# LED.net
KiCad netlist of a schematic drawn in Altium Designer
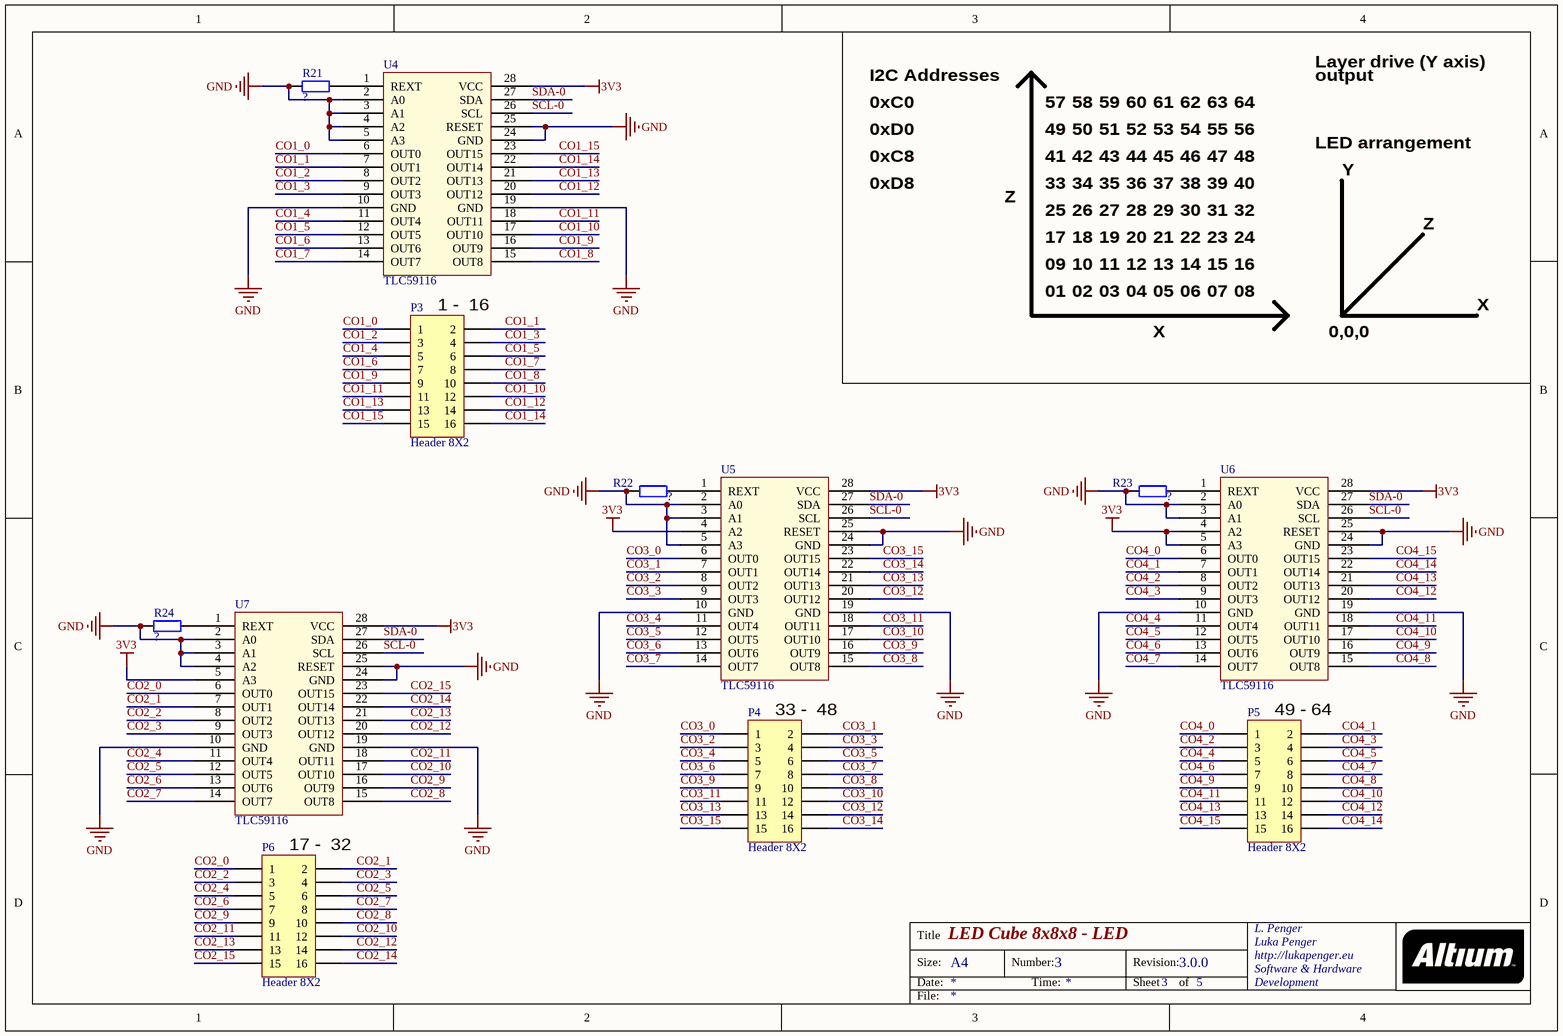
[diagram p0: LED.SchDoc]

(export (version "E")
  (design (tool "Eeschema 10.0.6"))
  (components
    (comp (ref "P3")
      (value "Header 8X2")
      (footprint "IDC-2x8")
      (description "Header, 8-Pin, Dual row")
      (fields (field (name "PUBLISHER") "Altium Limited"))
      (libsource (lib "Miscellaneous Connectors") (part "Header 8X2"))
    )
    (comp (ref "P4")
      (value "Header 8X2")
      (footprint "IDC-2x8")
      (description "Header, 8-Pin, Dual row")
      (fields (field (name "PUBLISHER") "Altium Limited"))
      (libsource (lib "Miscellaneous Connectors") (part "Header 8X2"))
    )
    (comp (ref "P5")
      (value "Header 8X2")
      (footprint "IDC-2x8")
      (description "Header, 8-Pin, Dual row")
      (fields (field (name "PUBLISHER") "Altium Limited"))
      (libsource (lib "Miscellaneous Connectors") (part "Header 8X2"))
    )
    (comp (ref "P6")
      (value "Header 8X2")
      (footprint "IDC-2x8")
      (description "Header, 8-Pin, Dual row")
      (fields (field (name "PUBLISHER") "Altium Limited"))
      (libsource (lib "Miscellaneous Connectors") (part "Header 8X2"))
    )
    (comp (ref "R21")
      (value "?")
      (footprint "1608[0603]")
      (description "Resistor")
      (fields (field (name "PUBLISHER") "Altium Limited"))
      (libsource (lib "Miscellaneous Devices") (part "Res2"))
    )
    (comp (ref "R22")
      (value "?")
      (footprint "1608[0603]")
      (description "Resistor")
      (fields (field (name "PUBLISHER") "Altium Limited"))
      (libsource (lib "") (part "Res2_1"))
    )
    (comp (ref "R23")
      (value "?")
      (footprint "1608[0603]")
      (description "Resistor")
      (fields (field (name "PUBLISHER") "Altium Limited"))
      (libsource (lib "") (part "Res2_1"))
    )
    (comp (ref "R24")
      (value "?")
      (footprint "1608[0603]")
      (description "Resistor")
      (fields (field (name "PUBLISHER") "Altium Limited"))
      (libsource (lib "Miscellaneous Devices") (part "Res2"))
    )
    (comp (ref "U4")
      (value "TLC59116")
      (footprint "TSSOP28")
      (description "16-Channel i2c LED driver")
      (libsource (lib "LukaLIBRARY") (part "TLC59116"))
    )
    (comp (ref "U5")
      (value "TLC59116")
      (footprint "TSSOP28")
      (description "16-Channel i2c LED driver")
      (libsource (lib "LukaLIBRARY") (part "TLC59116"))
    )
    (comp (ref "U6")
      (value "TLC59116")
      (footprint "TSSOP28")
      (description "16-Channel i2c LED driver")
      (libsource (lib "LukaLIBRARY") (part "TLC59116"))
    )
    (comp (ref "U7")
      (value "TLC59116")
      (footprint "TSSOP28")
      (description "16-Channel i2c LED driver")
      (libsource (lib "LukaLIBRARY") (part "TLC59116"))
    )
  )
  (nets
    (net (code "1") (name "/CO1_0") (class "Default")
      (node (ref "P3") (pin "1") (pinfunction "1_1") (pintype "passive"))
      (node (ref "U4") (pin "6") (pinfunction "OUT0_6") (pintype "passive"))
    )
    (net (code "2") (name "/CO1_1") (class "Default")
      (node (ref "P3") (pin "2") (pinfunction "2_2") (pintype "passive"))
      (node (ref "U4") (pin "7") (pinfunction "OUT1_7") (pintype "passive"))
    )
    (net (code "3") (name "/CO1_2") (class "Default")
      (node (ref "P3") (pin "3") (pinfunction "3_3") (pintype "passive"))
      (node (ref "U4") (pin "8") (pinfunction "OUT2_8") (pintype "passive"))
    )
    (net (code "4") (name "/CO1_3") (class "Default")
      (node (ref "P3") (pin "4") (pinfunction "4_4") (pintype "passive"))
      (node (ref "U4") (pin "9") (pinfunction "OUT3_9") (pintype "passive"))
    )
    (net (code "5") (name "/CO1_4") (class "Default")
      (node (ref "P3") (pin "5") (pinfunction "5_5") (pintype "passive"))
      (node (ref "U4") (pin "11") (pinfunction "OUT4_11") (pintype "passive"))
    )
    (net (code "6") (name "/CO1_5") (class "Default")
      (node (ref "P3") (pin "6") (pinfunction "6_6") (pintype "passive"))
      (node (ref "U4") (pin "12") (pinfunction "OUT5_12") (pintype "passive"))
    )
    (net (code "7") (name "/CO1_6") (class "Default")
      (node (ref "P3") (pin "7") (pinfunction "7_7") (pintype "passive"))
      (node (ref "U4") (pin "13") (pinfunction "OUT6_13") (pintype "passive"))
    )
    (net (code "8") (name "/CO1_7") (class "Default")
      (node (ref "P3") (pin "8") (pinfunction "8_8") (pintype "passive"))
      (node (ref "U4") (pin "14") (pinfunction "OUT7_14") (pintype "passive"))
    )
    (net (code "9") (name "/CO1_8") (class "Default")
      (node (ref "P3") (pin "10") (pinfunction "10_10") (pintype "passive"))
      (node (ref "U4") (pin "15") (pinfunction "OUT8_15") (pintype "passive"))
    )
    (net (code "10") (name "/CO1_9") (class "Default")
      (node (ref "P3") (pin "9") (pinfunction "9_9") (pintype "passive"))
      (node (ref "U4") (pin "16") (pinfunction "OUT9_16") (pintype "passive"))
    )
    (net (code "11") (name "/CO1_10") (class "Default")
      (node (ref "P3") (pin "12") (pinfunction "12_12") (pintype "passive"))
      (node (ref "U4") (pin "17") (pinfunction "OUT10_17") (pintype "passive"))
    )
    (net (code "12") (name "/CO1_11") (class "Default")
      (node (ref "P3") (pin "11") (pinfunction "11_11") (pintype "passive"))
      (node (ref "U4") (pin "18") (pinfunction "OUT11_18") (pintype "passive"))
    )
    (net (code "13") (name "/CO1_12") (class "Default")
      (node (ref "P3") (pin "14") (pinfunction "14_14") (pintype "passive"))
      (node (ref "U4") (pin "20") (pinfunction "OUT12_20") (pintype "passive"))
    )
    (net (code "14") (name "/CO1_13") (class "Default")
      (node (ref "P3") (pin "13") (pinfunction "13_13") (pintype "passive"))
      (node (ref "U4") (pin "21") (pinfunction "OUT13_21") (pintype "passive"))
    )
    (net (code "15") (name "/CO1_14") (class "Default")
      (node (ref "P3") (pin "16") (pinfunction "16_16") (pintype "passive"))
      (node (ref "U4") (pin "22") (pinfunction "OUT14_22") (pintype "passive"))
    )
    (net (code "16") (name "/CO1_15") (class "Default")
      (node (ref "P3") (pin "15") (pinfunction "15_15") (pintype "passive"))
      (node (ref "U4") (pin "23") (pinfunction "OUT15_23") (pintype "passive"))
    )
    (net (code "17") (name "/CO2_0") (class "Default")
      (node (ref "P6") (pin "1") (pinfunction "1_1") (pintype "passive"))
      (node (ref "U7") (pin "6") (pinfunction "OUT0_6") (pintype "passive"))
    )
    (net (code "18") (name "/CO2_1") (class "Default")
      (node (ref "P6") (pin "2") (pinfunction "2_2") (pintype "passive"))
      (node (ref "U7") (pin "7") (pinfunction "OUT1_7") (pintype "passive"))
    )
    (net (code "19") (name "/CO2_2") (class "Default")
      (node (ref "P6") (pin "3") (pinfunction "3_3") (pintype "passive"))
      (node (ref "U7") (pin "8") (pinfunction "OUT2_8") (pintype "passive"))
    )
    (net (code "20") (name "/CO2_3") (class "Default")
      (node (ref "P6") (pin "4") (pinfunction "4_4") (pintype "passive"))
      (node (ref "U7") (pin "9") (pinfunction "OUT3_9") (pintype "passive"))
    )
    (net (code "21") (name "/CO2_4") (class "Default")
      (node (ref "P6") (pin "5") (pinfunction "5_5") (pintype "passive"))
      (node (ref "U7") (pin "11") (pinfunction "OUT4_11") (pintype "passive"))
    )
    (net (code "22") (name "/CO2_5") (class "Default")
      (node (ref "P6") (pin "6") (pinfunction "6_6") (pintype "passive"))
      (node (ref "U7") (pin "12") (pinfunction "OUT5_12") (pintype "passive"))
    )
    (net (code "23") (name "/CO2_6") (class "Default")
      (node (ref "P6") (pin "7") (pinfunction "7_7") (pintype "passive"))
      (node (ref "U7") (pin "13") (pinfunction "OUT6_13") (pintype "passive"))
    )
    (net (code "24") (name "/CO2_7") (class "Default")
      (node (ref "P6") (pin "8") (pinfunction "8_8") (pintype "passive"))
      (node (ref "U7") (pin "14") (pinfunction "OUT7_14") (pintype "passive"))
    )
    (net (code "25") (name "/CO2_8") (class "Default")
      (node (ref "P6") (pin "10") (pinfunction "10_10") (pintype "passive"))
      (node (ref "U7") (pin "15") (pinfunction "OUT8_15") (pintype "passive"))
    )
    (net (code "26") (name "/CO2_9") (class "Default")
      (node (ref "P6") (pin "9") (pinfunction "9_9") (pintype "passive"))
      (node (ref "U7") (pin "16") (pinfunction "OUT9_16") (pintype "passive"))
    )
    (net (code "27") (name "/CO2_10") (class "Default")
      (node (ref "P6") (pin "12") (pinfunction "12_12") (pintype "passive"))
      (node (ref "U7") (pin "17") (pinfunction "OUT10_17") (pintype "passive"))
    )
    (net (code "28") (name "/CO2_11") (class "Default")
      (node (ref "P6") (pin "11") (pinfunction "11_11") (pintype "passive"))
      (node (ref "U7") (pin "18") (pinfunction "OUT11_18") (pintype "passive"))
    )
    (net (code "29") (name "/CO2_12") (class "Default")
      (node (ref "P6") (pin "14") (pinfunction "14_14") (pintype "passive"))
      (node (ref "U7") (pin "20") (pinfunction "OUT12_20") (pintype "passive"))
    )
    (net (code "30") (name "/CO2_13") (class "Default")
      (node (ref "P6") (pin "13") (pinfunction "13_13") (pintype "passive"))
      (node (ref "U7") (pin "21") (pinfunction "OUT13_21") (pintype "passive"))
    )
    (net (code "31") (name "/CO2_14") (class "Default")
      (node (ref "P6") (pin "16") (pinfunction "16_16") (pintype "passive"))
      (node (ref "U7") (pin "22") (pinfunction "OUT14_22") (pintype "passive"))
    )
    (net (code "32") (name "/CO2_15") (class "Default")
      (node (ref "P6") (pin "15") (pinfunction "15_15") (pintype "passive"))
      (node (ref "U7") (pin "23") (pinfunction "OUT15_23") (pintype "passive"))
    )
    (net (code "33") (name "/CO3_0") (class "Default")
      (node (ref "P4") (pin "1") (pinfunction "1_1") (pintype "passive"))
      (node (ref "U5") (pin "6") (pinfunction "OUT0_6") (pintype "passive"))
    )
    (net (code "34") (name "/CO3_1") (class "Default")
      (node (ref "P4") (pin "2") (pinfunction "2_2") (pintype "passive"))
      (node (ref "U5") (pin "7") (pinfunction "OUT1_7") (pintype "passive"))
    )
    (net (code "35") (name "/CO3_2") (class "Default")
      (node (ref "P4") (pin "3") (pinfunction "3_3") (pintype "passive"))
      (node (ref "U5") (pin "8") (pinfunction "OUT2_8") (pintype "passive"))
    )
    (net (code "36") (name "/CO3_3") (class "Default")
      (node (ref "P4") (pin "4") (pinfunction "4_4") (pintype "passive"))
      (node (ref "U5") (pin "9") (pinfunction "OUT3_9") (pintype "passive"))
    )
    (net (code "37") (name "/CO3_4") (class "Default")
      (node (ref "P4") (pin "5") (pinfunction "5_5") (pintype "passive"))
      (node (ref "U5") (pin "11") (pinfunction "OUT4_11") (pintype "passive"))
    )
    (net (code "38") (name "/CO3_5") (class "Default")
      (node (ref "P4") (pin "6") (pinfunction "6_6") (pintype "passive"))
      (node (ref "U5") (pin "12") (pinfunction "OUT5_12") (pintype "passive"))
    )
    (net (code "39") (name "/CO3_6") (class "Default")
      (node (ref "P4") (pin "7") (pinfunction "7_7") (pintype "passive"))
      (node (ref "U5") (pin "13") (pinfunction "OUT6_13") (pintype "passive"))
    )
    (net (code "40") (name "/CO3_7") (class "Default")
      (node (ref "P4") (pin "8") (pinfunction "8_8") (pintype "passive"))
      (node (ref "U5") (pin "14") (pinfunction "OUT7_14") (pintype "passive"))
    )
    (net (code "41") (name "/CO3_8") (class "Default")
      (node (ref "P4") (pin "10") (pinfunction "10_10") (pintype "passive"))
      (node (ref "U5") (pin "15") (pinfunction "OUT8_15") (pintype "passive"))
    )
    (net (code "42") (name "/CO3_9") (class "Default")
      (node (ref "P4") (pin "9") (pinfunction "9_9") (pintype "passive"))
      (node (ref "U5") (pin "16") (pinfunction "OUT9_16") (pintype "passive"))
    )
    (net (code "43") (name "/CO3_10") (class "Default")
      (node (ref "P4") (pin "12") (pinfunction "12_12") (pintype "passive"))
      (node (ref "U5") (pin "17") (pinfunction "OUT10_17") (pintype "passive"))
    )
    (net (code "44") (name "/CO3_11") (class "Default")
      (node (ref "P4") (pin "11") (pinfunction "11_11") (pintype "passive"))
      (node (ref "U5") (pin "18") (pinfunction "OUT11_18") (pintype "passive"))
    )
    (net (code "45") (name "/CO3_12") (class "Default")
      (node (ref "P4") (pin "14") (pinfunction "14_14") (pintype "passive"))
      (node (ref "U5") (pin "20") (pinfunction "OUT12_20") (pintype "passive"))
    )
    (net (code "46") (name "/CO3_13") (class "Default")
      (node (ref "P4") (pin "13") (pinfunction "13_13") (pintype "passive"))
      (node (ref "U5") (pin "21") (pinfunction "OUT13_21") (pintype "passive"))
    )
    (net (code "47") (name "/CO3_14") (class "Default")
      (node (ref "P4") (pin "16") (pinfunction "16_16") (pintype "passive"))
      (node (ref "U5") (pin "22") (pinfunction "OUT14_22") (pintype "passive"))
    )
    (net (code "48") (name "/CO3_15") (class "Default")
      (node (ref "P4") (pin "15") (pinfunction "15_15") (pintype "passive"))
      (node (ref "U5") (pin "23") (pinfunction "OUT15_23") (pintype "passive"))
    )
    (net (code "49") (name "/CO4_0") (class "Default")
      (node (ref "P5") (pin "1") (pinfunction "1_1") (pintype "passive"))
      (node (ref "U6") (pin "6") (pinfunction "OUT0_6") (pintype "passive"))
    )
    (net (code "50") (name "/CO4_1") (class "Default")
      (node (ref "P5") (pin "2") (pinfunction "2_2") (pintype "passive"))
      (node (ref "U6") (pin "7") (pinfunction "OUT1_7") (pintype "passive"))
    )
    (net (code "51") (name "/CO4_2") (class "Default")
      (node (ref "P5") (pin "3") (pinfunction "3_3") (pintype "passive"))
      (node (ref "U6") (pin "8") (pinfunction "OUT2_8") (pintype "passive"))
    )
    (net (code "52") (name "/CO4_3") (class "Default")
      (node (ref "P5") (pin "4") (pinfunction "4_4") (pintype "passive"))
      (node (ref "U6") (pin "9") (pinfunction "OUT3_9") (pintype "passive"))
    )
    (net (code "53") (name "/CO4_4") (class "Default")
      (node (ref "P5") (pin "5") (pinfunction "5_5") (pintype "passive"))
      (node (ref "U6") (pin "11") (pinfunction "OUT4_11") (pintype "passive"))
    )
    (net (code "54") (name "/CO4_5") (class "Default")
      (node (ref "P5") (pin "6") (pinfunction "6_6") (pintype "passive"))
      (node (ref "U6") (pin "12") (pinfunction "OUT5_12") (pintype "passive"))
    )
    (net (code "55") (name "/CO4_6") (class "Default")
      (node (ref "P5") (pin "7") (pinfunction "7_7") (pintype "passive"))
      (node (ref "U6") (pin "13") (pinfunction "OUT6_13") (pintype "passive"))
    )
    (net (code "56") (name "/CO4_7") (class "Default")
      (node (ref "P5") (pin "8") (pinfunction "8_8") (pintype "passive"))
      (node (ref "U6") (pin "14") (pinfunction "OUT7_14") (pintype "passive"))
    )
    (net (code "57") (name "/CO4_8") (class "Default")
      (node (ref "P5") (pin "10") (pinfunction "10_10") (pintype "passive"))
      (node (ref "U6") (pin "15") (pinfunction "OUT8_15") (pintype "passive"))
    )
    (net (code "58") (name "/CO4_9") (class "Default")
      (node (ref "P5") (pin "9") (pinfunction "9_9") (pintype "passive"))
      (node (ref "U6") (pin "16") (pinfunction "OUT9_16") (pintype "passive"))
    )
    (net (code "59") (name "/CO4_10") (class "Default")
      (node (ref "P5") (pin "12") (pinfunction "12_12") (pintype "passive"))
      (node (ref "U6") (pin "17") (pinfunction "OUT10_17") (pintype "passive"))
    )
    (net (code "60") (name "/CO4_11") (class "Default")
      (node (ref "P5") (pin "11") (pinfunction "11_11") (pintype "passive"))
      (node (ref "U6") (pin "18") (pinfunction "OUT11_18") (pintype "passive"))
    )
    (net (code "61") (name "/CO4_12") (class "Default")
      (node (ref "P5") (pin "14") (pinfunction "14_14") (pintype "passive"))
      (node (ref "U6") (pin "20") (pinfunction "OUT12_20") (pintype "passive"))
    )
    (net (code "62") (name "/CO4_13") (class "Default")
      (node (ref "P5") (pin "13") (pinfunction "13_13") (pintype "passive"))
      (node (ref "U6") (pin "21") (pinfunction "OUT13_21") (pintype "passive"))
    )
    (net (code "63") (name "/CO4_14") (class "Default")
      (node (ref "P5") (pin "16") (pinfunction "16_16") (pintype "passive"))
      (node (ref "U6") (pin "22") (pinfunction "OUT14_22") (pintype "passive"))
    )
    (net (code "64") (name "/CO4_15") (class "Default")
      (node (ref "P5") (pin "15") (pinfunction "15_15") (pintype "passive"))
      (node (ref "U6") (pin "23") (pinfunction "OUT15_23") (pintype "passive"))
    )
    (net (code "65") (name "/SCL-0") (class "Default")
      (node (ref "U4") (pin "26") (pinfunction "SCL_26") (pintype "passive"))
      (node (ref "U5") (pin "26") (pinfunction "SCL_26") (pintype "passive"))
      (node (ref "U6") (pin "26") (pinfunction "SCL_26") (pintype "passive"))
      (node (ref "U7") (pin "26") (pinfunction "SCL_26") (pintype "passive"))
    )
    (net (code "66") (name "/SDA-0") (class "Default")
      (node (ref "U4") (pin "27") (pinfunction "SDA_27") (pintype "passive"))
      (node (ref "U5") (pin "27") (pinfunction "SDA_27") (pintype "passive"))
      (node (ref "U6") (pin "27") (pinfunction "SDA_27") (pintype "passive"))
      (node (ref "U7") (pin "27") (pinfunction "SDA_27") (pintype "passive"))
    )
    (net (code "67") (name "3V3") (class "Default")
      (node (ref "U4") (pin "28") (pinfunction "VCC_28") (pintype "passive"))
      (node (ref "U5") (pin "28") (pinfunction "VCC_28") (pintype "passive"))
      (node (ref "U5") (pin "4") (pinfunction "A2_4") (pintype "passive"))
      (node (ref "U6") (pin "28") (pinfunction "VCC_28") (pintype "passive"))
      (node (ref "U6") (pin "4") (pinfunction "A2_4") (pintype "passive"))
      (node (ref "U6") (pin "5") (pinfunction "A3_5") (pintype "passive"))
      (node (ref "U7") (pin "28") (pinfunction "VCC_28") (pintype "passive"))
      (node (ref "U7") (pin "5") (pinfunction "A3_5") (pintype "passive"))
    )
    (net (code "68") (name "GND") (class "Default")
      (node (ref "R21") (pin "2") (pinfunction "2_2") (pintype "passive"))
      (node (ref "R22") (pin "1") (pinfunction "1_1") (pintype "passive"))
      (node (ref "R23") (pin "1") (pinfunction "1_1") (pintype "passive"))
      (node (ref "R24") (pin "2") (pinfunction "2_2") (pintype "passive"))
      (node (ref "U4") (pin "10") (pinfunction "GND_10") (pintype "passive"))
      (node (ref "U4") (pin "19") (pinfunction "GND_19") (pintype "passive"))
      (node (ref "U4") (pin "2") (pinfunction "A0_2") (pintype "passive"))
      (node (ref "U4") (pin "24") (pinfunction "GND_24") (pintype "passive"))
      (node (ref "U4") (pin "25") (pinfunction "RESET_25") (pintype "passive"))
      (node (ref "U4") (pin "3") (pinfunction "A1_3") (pintype "passive"))
      (node (ref "U4") (pin "4") (pinfunction "A2_4") (pintype "passive"))
      (node (ref "U4") (pin "5") (pinfunction "A3_5") (pintype "passive"))
      (node (ref "U5") (pin "10") (pinfunction "GND_10") (pintype "passive"))
      (node (ref "U5") (pin "19") (pinfunction "GND_19") (pintype "passive"))
      (node (ref "U5") (pin "2") (pinfunction "A0_2") (pintype "passive"))
      (node (ref "U5") (pin "24") (pinfunction "GND_24") (pintype "passive"))
      (node (ref "U5") (pin "25") (pinfunction "RESET_25") (pintype "passive"))
      (node (ref "U5") (pin "3") (pinfunction "A1_3") (pintype "passive"))
      (node (ref "U5") (pin "5") (pinfunction "A3_5") (pintype "passive"))
      (node (ref "U6") (pin "10") (pinfunction "GND_10") (pintype "passive"))
      (node (ref "U6") (pin "19") (pinfunction "GND_19") (pintype "passive"))
      (node (ref "U6") (pin "2") (pinfunction "A0_2") (pintype "passive"))
      (node (ref "U6") (pin "24") (pinfunction "GND_24") (pintype "passive"))
      (node (ref "U6") (pin "25") (pinfunction "RESET_25") (pintype "passive"))
      (node (ref "U6") (pin "3") (pinfunction "A1_3") (pintype "passive"))
      (node (ref "U7") (pin "10") (pinfunction "GND_10") (pintype "passive"))
      (node (ref "U7") (pin "19") (pinfunction "GND_19") (pintype "passive"))
      (node (ref "U7") (pin "2") (pinfunction "A0_2") (pintype "passive"))
      (node (ref "U7") (pin "24") (pinfunction "GND_24") (pintype "passive"))
      (node (ref "U7") (pin "25") (pinfunction "RESET_25") (pintype "passive"))
      (node (ref "U7") (pin "3") (pinfunction "A1_3") (pintype "passive"))
      (node (ref "U7") (pin "4") (pinfunction "A2_4") (pintype "passive"))
    )
    (net (code "69") (name "Net-(U4-REXT)") (class "Default")
      (node (ref "R21") (pin "1") (pinfunction "1_1") (pintype "passive"))
      (node (ref "U4") (pin "1") (pinfunction "REXT_1") (pintype "passive"))
    )
    (net (code "70") (name "Net-(U5-REXT)") (class "Default")
      (node (ref "R22") (pin "2") (pinfunction "2_2") (pintype "passive"))
      (node (ref "U5") (pin "1") (pinfunction "REXT_1") (pintype "passive"))
    )
    (net (code "71") (name "Net-(U6-REXT)") (class "Default")
      (node (ref "R23") (pin "2") (pinfunction "2_2") (pintype "passive"))
      (node (ref "U6") (pin "1") (pinfunction "REXT_1") (pintype "passive"))
    )
    (net (code "72") (name "Net-(U7-REXT)") (class "Default")
      (node (ref "R24") (pin "1") (pinfunction "1_1") (pintype "passive"))
      (node (ref "U7") (pin "1") (pinfunction "REXT_1") (pintype "passive"))
    )
  )
)
